# TTGO_shield_revC.net
KiCad netlist of a schematic drawn in EAGLE
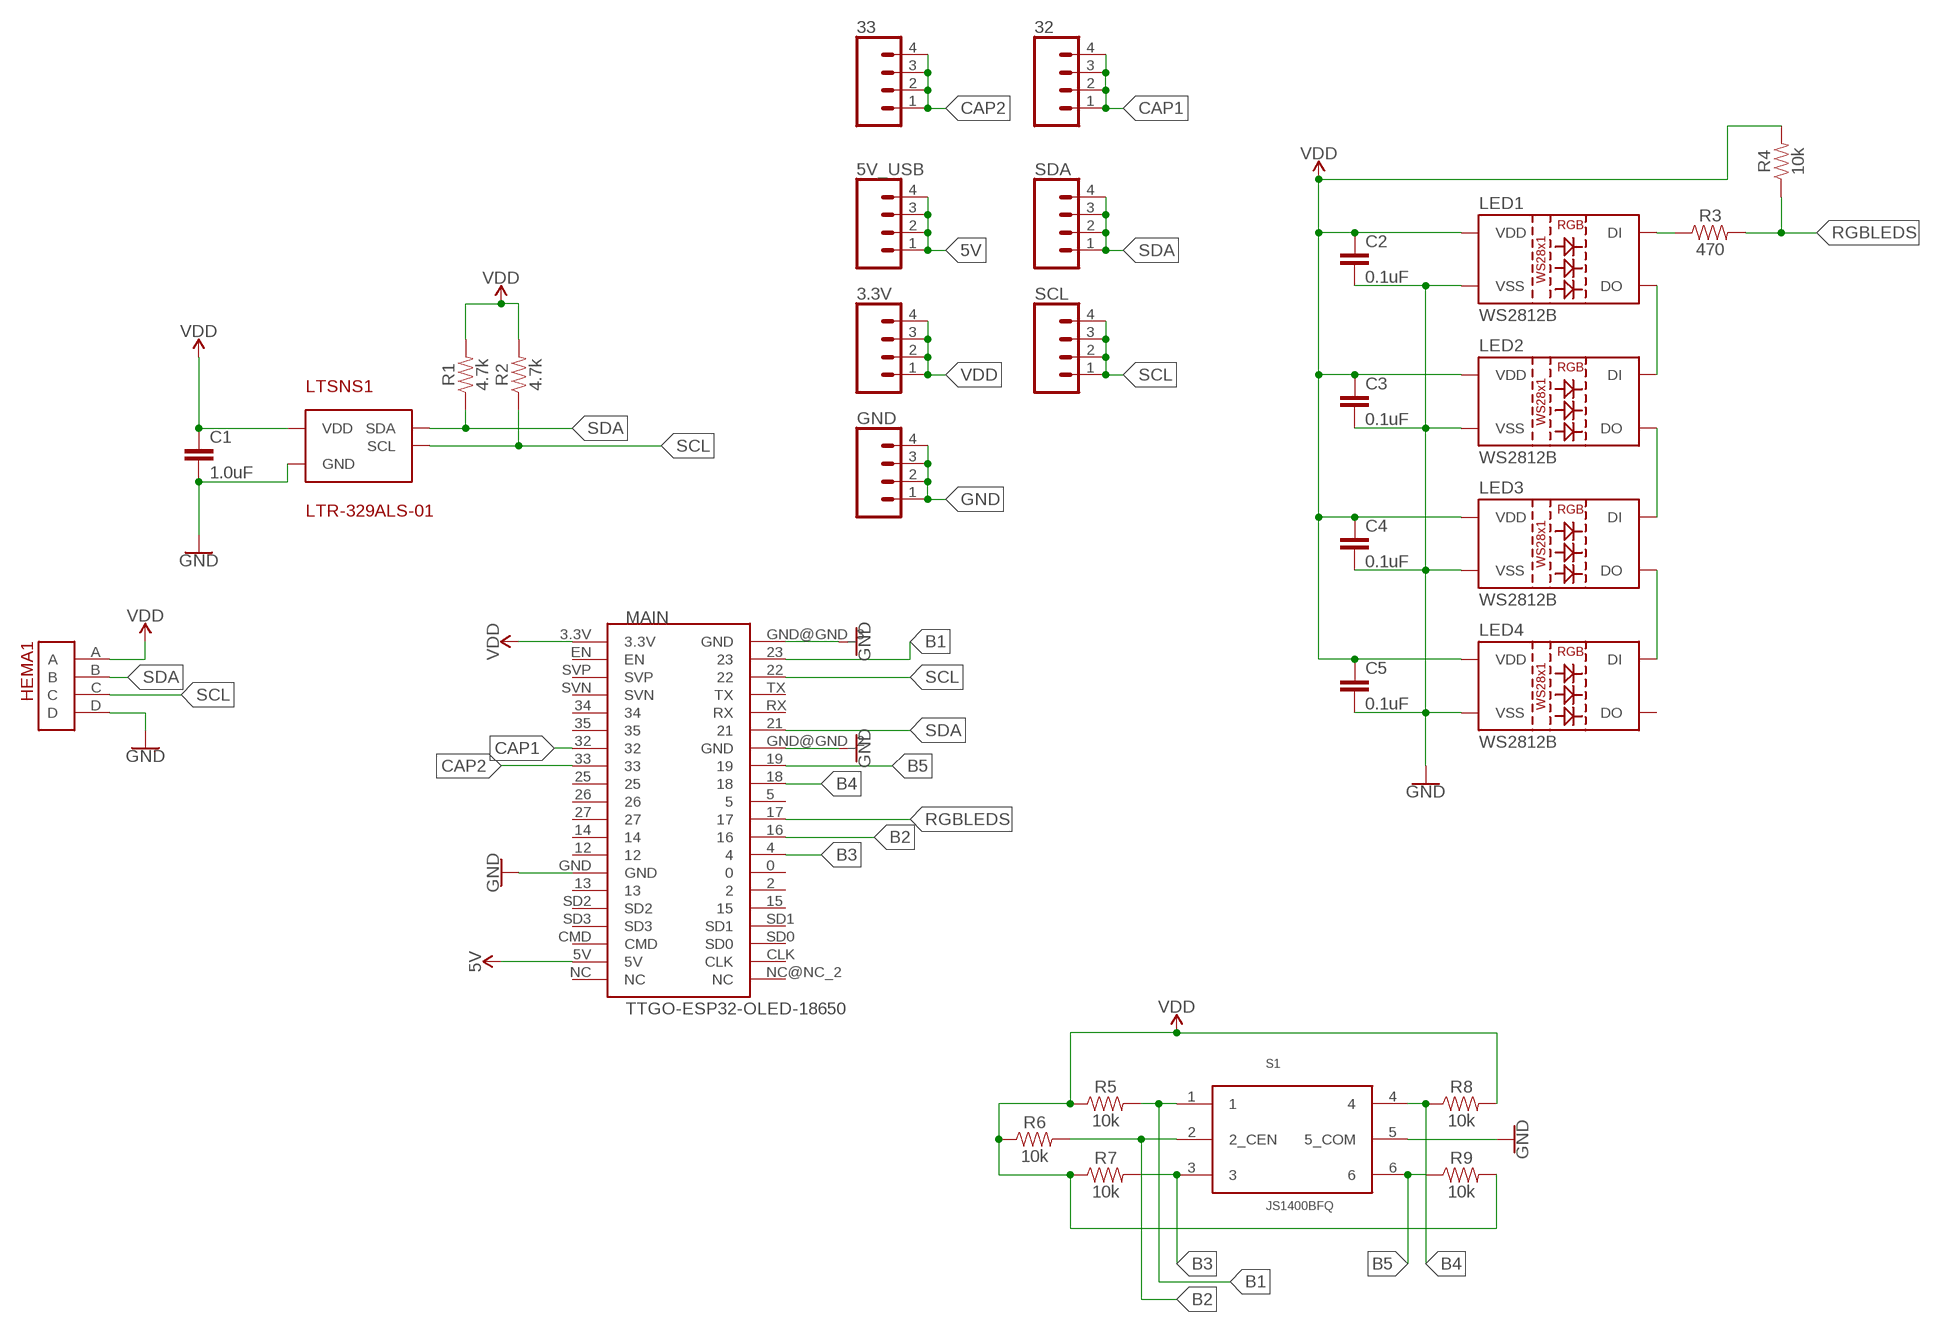
[diagram p0: schematic, sheet 1]

(export (version "E")
  (design (tool "Eeschema 10.0.6"))
  (components
    (comp (ref "3.3V")
      (value "CONN_041X04_NO_SILK")
      (footprint "eagle-import:1X04_NO_SILK")
      (libsource (lib "eagle-import") (part "CONN_041X04_NO_SILK"))
    )
    (comp (ref "5V_USB")
      (value "CONN_041X04_NO_SILK")
      (footprint "eagle-import:1X04_NO_SILK")
      (libsource (lib "eagle-import") (part "CONN_041X04_NO_SILK"))
    )
    (comp (ref "32")
      (value "CONN_041X04_NO_SILK")
      (footprint "eagle-import:1X04_NO_SILK")
      (libsource (lib "eagle-import") (part "CONN_041X04_NO_SILK"))
    )
    (comp (ref "33")
      (value "CONN_041X04_NO_SILK")
      (footprint "eagle-import:1X04_NO_SILK")
      (libsource (lib "eagle-import") (part "CONN_041X04_NO_SILK"))
    )
    (comp (ref "C1")
      (value "1.0uF")
      (footprint "eagle-import:0805")
      (libsource (lib "eagle-import") (part "1.0UF-0805-25V-10%"))
    )
    (comp (ref "C2")
      (value "0.1uF")
      (footprint "eagle-import:0603")
      (libsource (lib "eagle-import") (part "0.1UF-0603-25V-5%"))
    )
    (comp (ref "C3")
      (value "0.1uF")
      (footprint "eagle-import:0603")
      (libsource (lib "eagle-import") (part "0.1UF-0603-25V-5%"))
    )
    (comp (ref "C4")
      (value "0.1uF")
      (footprint "eagle-import:0603")
      (libsource (lib "eagle-import") (part "0.1UF-0603-25V-5%"))
    )
    (comp (ref "C5")
      (value "0.1uF")
      (footprint "eagle-import:0603")
      (libsource (lib "eagle-import") (part "0.1UF-0603-25V-5%"))
    )
    (comp (ref "GND")
      (value "CONN_041X04_NO_SILK")
      (footprint "eagle-import:1X04_NO_SILK")
      (libsource (lib "eagle-import") (part "CONN_041X04_NO_SILK"))
    )
    (comp (ref "HEMA1")
      (value "10120045-400LF")
      (footprint "eagle-import:10120045-400LF")
      (libsource (lib "eagle-import") (part "10120045-400LF"))
    )
    (comp (ref "LED1")
      (value "WS2812B")
      (footprint "eagle-import:WS2812B")
      (libsource (lib "eagle-import") (part "WS2812B"))
    )
    (comp (ref "LED2")
      (value "WS2812B")
      (footprint "eagle-import:WS2812B")
      (libsource (lib "eagle-import") (part "WS2812B"))
    )
    (comp (ref "LED3")
      (value "WS2812B")
      (footprint "eagle-import:WS2812B")
      (libsource (lib "eagle-import") (part "WS2812B"))
    )
    (comp (ref "LED4")
      (value "WS2812B")
      (footprint "eagle-import:WS2812B")
      (libsource (lib "eagle-import") (part "WS2812B"))
    )
    (comp (ref "LTSNS1")
      (value "LTR-329ALS-01")
      (footprint "eagle-import:CHIPLED-4")
      (libsource (lib "eagle-import") (part "LTR-329ALS-01"))
    )
    (comp (ref "MAIN")
      (value "TTGO-ESP32-OLED-18650")
      (footprint "eagle-import:TTGO-ESP32-OLED-18650")
      (libsource (lib "eagle-import") (part "TTGO-ESP32-OLED-18650"))
    )
    (comp (ref "R1")
      (value "4.7k")
      (footprint "eagle-import:0603")
      (libsource (lib "eagle-import") (part "4.7KOHM-0603-1/10W-1%"))
    )
    (comp (ref "R2")
      (value "4.7k")
      (footprint "eagle-import:0603")
      (libsource (lib "eagle-import") (part "4.7KOHM-0603-1/10W-1%"))
    )
    (comp (ref "R3")
      (value "470")
      (footprint "eagle-import:0603")
      (libsource (lib "eagle-import") (part "470OHM-0603-1/10W-1%"))
    )
    (comp (ref "R4")
      (value "10k")
      (footprint "eagle-import:0603")
      (libsource (lib "eagle-import") (part "10KOHM-0603-1/10W-1%"))
    )
    (comp (ref "R5")
      (value "10k")
      (footprint "eagle-import:0603")
      (libsource (lib "eagle-import") (part "10KOHM-0603-1/10W-1%"))
    )
    (comp (ref "R6")
      (value "10k")
      (footprint "eagle-import:0603")
      (libsource (lib "eagle-import") (part "10KOHM-0603-1/10W-1%"))
    )
    (comp (ref "R7")
      (value "10k")
      (footprint "eagle-import:0603")
      (libsource (lib "eagle-import") (part "10KOHM-0603-1/10W-1%"))
    )
    (comp (ref "R8")
      (value "10k")
      (footprint "eagle-import:0603")
      (libsource (lib "eagle-import") (part "10KOHM-0603-1/10W-1%"))
    )
    (comp (ref "R9")
      (value "10k")
      (footprint "eagle-import:0603")
      (libsource (lib "eagle-import") (part "10KOHM-0603-1/10W-1%"))
    )
    (comp (ref "S1")
      (value "JS1400BFQ")
      (footprint "eagle-import:JS1400BFQ")
      (libsource (lib "eagle-import") (part "JS1400BFQ"))
    )
    (comp (ref "SCL")
      (value "CONN_041X04_NO_SILK")
      (footprint "eagle-import:1X04_NO_SILK")
      (libsource (lib "eagle-import") (part "CONN_041X04_NO_SILK"))
    )
    (comp (ref "SDA")
      (value "CONN_041X04_NO_SILK")
      (footprint "eagle-import:1X04_NO_SILK")
      (libsource (lib "eagle-import") (part "CONN_041X04_NO_SILK"))
    )
  )
  (nets
    (net (code "1") (name "5V") (class "Default")
      (node (ref "5V_USB") (pin "1") (pinfunction "1_1") (pintype "passive"))
      (node (ref "5V_USB") (pin "2") (pinfunction "2_2") (pintype "passive"))
      (node (ref "5V_USB") (pin "3") (pinfunction "3_3") (pintype "passive"))
      (node (ref "5V_USB") (pin "4") (pinfunction "4_4") (pintype "passive"))
      (node (ref "MAIN") (pin "5V") (pinfunction "5V_5V") (pintype "bidirectional"))
    )
    (net (code "2") (name "B1") (class "Default")
      (node (ref "MAIN") (pin "23") (pinfunction "23_23") (pintype "bidirectional"))
      (node (ref "R5") (pin "2") (pinfunction "2_2") (pintype "passive"))
      (node (ref "S1") (pin "1") (pinfunction "1_1") (pintype "bidirectional"))
    )
    (net (code "3") (name "B2") (class "Default")
      (node (ref "MAIN") (pin "16") (pinfunction "16_16") (pintype "bidirectional"))
      (node (ref "R6") (pin "2") (pinfunction "2_2") (pintype "passive"))
      (node (ref "S1") (pin "2") (pinfunction "2_CEN_2") (pintype "bidirectional"))
    )
    (net (code "4") (name "B3") (class "Default")
      (node (ref "MAIN") (pin "4") (pinfunction "4_4") (pintype "bidirectional"))
      (node (ref "R7") (pin "2") (pinfunction "2_2") (pintype "passive"))
      (node (ref "S1") (pin "3") (pinfunction "3_3") (pintype "bidirectional"))
    )
    (net (code "5") (name "B4") (class "Default")
      (node (ref "MAIN") (pin "18") (pinfunction "18_18") (pintype "bidirectional"))
      (node (ref "R8") (pin "1") (pinfunction "1_1") (pintype "passive"))
      (node (ref "S1") (pin "4") (pinfunction "4_4") (pintype "bidirectional"))
    )
    (net (code "6") (name "B5") (class "Default")
      (node (ref "MAIN") (pin "19") (pinfunction "19_19") (pintype "bidirectional"))
      (node (ref "R9") (pin "1") (pinfunction "1_1") (pintype "passive"))
      (node (ref "S1") (pin "6") (pinfunction "6_6") (pintype "bidirectional"))
    )
    (net (code "7") (name "CAP1") (class "Default")
      (node (ref "32") (pin "1") (pinfunction "1_1") (pintype "passive"))
      (node (ref "32") (pin "2") (pinfunction "2_2") (pintype "passive"))
      (node (ref "32") (pin "3") (pinfunction "3_3") (pintype "passive"))
      (node (ref "32") (pin "4") (pinfunction "4_4") (pintype "passive"))
      (node (ref "MAIN") (pin "32") (pinfunction "32_32") (pintype "bidirectional"))
    )
    (net (code "8") (name "CAP2") (class "Default")
      (node (ref "33") (pin "1") (pinfunction "1_1") (pintype "passive"))
      (node (ref "33") (pin "2") (pinfunction "2_2") (pintype "passive"))
      (node (ref "33") (pin "3") (pinfunction "3_3") (pintype "passive"))
      (node (ref "33") (pin "4") (pinfunction "4_4") (pintype "passive"))
      (node (ref "MAIN") (pin "33") (pinfunction "33_33") (pintype "bidirectional"))
    )
    (net (code "9") (name "GND") (class "Default")
      (node (ref "C1") (pin "2") (pinfunction "2_2") (pintype "passive"))
      (node (ref "C2") (pin "2") (pinfunction "2_2") (pintype "passive"))
      (node (ref "C3") (pin "2") (pinfunction "2_2") (pintype "passive"))
      (node (ref "C4") (pin "2") (pinfunction "2_2") (pintype "passive"))
      (node (ref "C5") (pin "2") (pinfunction "2_2") (pintype "passive"))
      (node (ref "GND") (pin "1") (pinfunction "1_1") (pintype "passive"))
      (node (ref "GND") (pin "2") (pinfunction "2_2") (pintype "passive"))
      (node (ref "GND") (pin "3") (pinfunction "3_3") (pintype "passive"))
      (node (ref "GND") (pin "4") (pinfunction "4_4") (pintype "passive"))
      (node (ref "HEMA1") (pin "D") (pinfunction "D_D") (pintype "bidirectional"))
      (node (ref "LED1") (pin "3") (pinfunction "VSS_3") (pintype "bidirectional"))
      (node (ref "LED2") (pin "3") (pinfunction "VSS_3") (pintype "bidirectional"))
      (node (ref "LED3") (pin "3") (pinfunction "VSS_3") (pintype "bidirectional"))
      (node (ref "LED4") (pin "3") (pinfunction "VSS_3") (pintype "bidirectional"))
      (node (ref "LTSNS1") (pin "2") (pinfunction "GND_2") (pintype "bidirectional"))
      (node (ref "MAIN") (pin "GND") (pinfunction "GND_GND") (pintype "bidirectional"))
      (node (ref "MAIN") (pin "GND@GND_2") (pinfunction "GND_GND@GND_2") (pintype "bidirectional"))
      (node (ref "MAIN") (pin "GND@GND_3") (pinfunction "GND_GND@GND_3") (pintype "bidirectional"))
      (node (ref "S1") (pin "5") (pinfunction "5_COM_5") (pintype "bidirectional"))
    )
    (net (code "10") (name "Net-(LED1-DI)") (class "Default")
      (node (ref "LED1") (pin "4") (pinfunction "DI_4") (pintype "bidirectional"))
      (node (ref "R3") (pin "1") (pinfunction "1_1") (pintype "passive"))
    )
    (net (code "11") (name "Net-(LED1-DO)") (class "Default")
      (node (ref "LED1") (pin "2") (pinfunction "DO_2") (pintype "bidirectional"))
      (node (ref "LED2") (pin "4") (pinfunction "DI_4") (pintype "bidirectional"))
    )
    (net (code "12") (name "Net-(LED2-DO)") (class "Default")
      (node (ref "LED2") (pin "2") (pinfunction "DO_2") (pintype "bidirectional"))
      (node (ref "LED3") (pin "4") (pinfunction "DI_4") (pintype "bidirectional"))
    )
    (net (code "13") (name "Net-(LED3-DO)") (class "Default")
      (node (ref "LED3") (pin "2") (pinfunction "DO_2") (pintype "bidirectional"))
      (node (ref "LED4") (pin "4") (pinfunction "DI_4") (pintype "bidirectional"))
    )
    (net (code "14") (name "RGBLEDS") (class "Default")
      (node (ref "MAIN") (pin "17") (pinfunction "17_17") (pintype "bidirectional"))
      (node (ref "R3") (pin "2") (pinfunction "2_2") (pintype "passive"))
      (node (ref "R4") (pin "1") (pinfunction "1_1") (pintype "passive"))
    )
    (net (code "15") (name "SCL") (class "Default")
      (node (ref "HEMA1") (pin "C") (pinfunction "C_C") (pintype "bidirectional"))
      (node (ref "LTSNS1") (pin "4") (pinfunction "SCL_4") (pintype "bidirectional"))
      (node (ref "MAIN") (pin "22") (pinfunction "22_22") (pintype "bidirectional"))
      (node (ref "R2") (pin "1") (pinfunction "1_1") (pintype "passive"))
      (node (ref "SCL") (pin "1") (pinfunction "1_1") (pintype "passive"))
      (node (ref "SCL") (pin "2") (pinfunction "2_2") (pintype "passive"))
      (node (ref "SCL") (pin "3") (pinfunction "3_3") (pintype "passive"))
      (node (ref "SCL") (pin "4") (pinfunction "4_4") (pintype "passive"))
    )
    (net (code "16") (name "SDA") (class "Default")
      (node (ref "HEMA1") (pin "B") (pinfunction "B_B") (pintype "bidirectional"))
      (node (ref "LTSNS1") (pin "3") (pinfunction "SDA_3") (pintype "bidirectional"))
      (node (ref "MAIN") (pin "21") (pinfunction "21_21") (pintype "bidirectional"))
      (node (ref "R1") (pin "1") (pinfunction "1_1") (pintype "passive"))
      (node (ref "SDA") (pin "1") (pinfunction "1_1") (pintype "passive"))
      (node (ref "SDA") (pin "2") (pinfunction "2_2") (pintype "passive"))
      (node (ref "SDA") (pin "3") (pinfunction "3_3") (pintype "passive"))
      (node (ref "SDA") (pin "4") (pinfunction "4_4") (pintype "passive"))
    )
    (net (code "17") (name "VDD") (class "Default")
      (node (ref "3.3V") (pin "1") (pinfunction "1_1") (pintype "passive"))
      (node (ref "3.3V") (pin "2") (pinfunction "2_2") (pintype "passive"))
      (node (ref "3.3V") (pin "3") (pinfunction "3_3") (pintype "passive"))
      (node (ref "3.3V") (pin "4") (pinfunction "4_4") (pintype "passive"))
      (node (ref "C1") (pin "1") (pinfunction "1_1") (pintype "passive"))
      (node (ref "C2") (pin "1") (pinfunction "1_1") (pintype "passive"))
      (node (ref "C3") (pin "1") (pinfunction "1_1") (pintype "passive"))
      (node (ref "C4") (pin "1") (pinfunction "1_1") (pintype "passive"))
      (node (ref "C5") (pin "1") (pinfunction "1_1") (pintype "passive"))
      (node (ref "HEMA1") (pin "A") (pinfunction "A_A") (pintype "bidirectional"))
      (node (ref "LED1") (pin "1") (pinfunction "VDD_1") (pintype "bidirectional"))
      (node (ref "LED2") (pin "1") (pinfunction "VDD_1") (pintype "bidirectional"))
      (node (ref "LED3") (pin "1") (pinfunction "VDD_1") (pintype "bidirectional"))
      (node (ref "LED4") (pin "1") (pinfunction "VDD_1") (pintype "bidirectional"))
      (node (ref "LTSNS1") (pin "1") (pinfunction "VDD_1") (pintype "bidirectional"))
      (node (ref "MAIN") (pin "3.3V") (pinfunction "3.3V_3.3V") (pintype "bidirectional"))
      (node (ref "R1") (pin "2") (pinfunction "2_2") (pintype "passive"))
      (node (ref "R2") (pin "2") (pinfunction "2_2") (pintype "passive"))
      (node (ref "R4") (pin "2") (pinfunction "2_2") (pintype "passive"))
      (node (ref "R5") (pin "1") (pinfunction "1_1") (pintype "passive"))
      (node (ref "R6") (pin "1") (pinfunction "1_1") (pintype "passive"))
      (node (ref "R7") (pin "1") (pinfunction "1_1") (pintype "passive"))
      (node (ref "R8") (pin "2") (pinfunction "2_2") (pintype "passive"))
      (node (ref "R9") (pin "2") (pinfunction "2_2") (pintype "passive"))
    )
    (net (code "18") (name "unconnected-(LED4-DO-Pad2)") (class "Default")
      (node (ref "LED4") (pin "2") (pinfunction "DO_2") (pintype "bidirectional"))
    )
    (net (code "19") (name "unconnected-(MAIN-NC-PadNC@NC_2)") (class "Default")
      (node (ref "MAIN") (pin "NC@NC_2") (pinfunction "NC_NC@NC_2") (pintype "bidirectional"))
    )
    (net (code "20") (name "unconnected-(MAIN-Pad0)") (class "Default")
      (node (ref "MAIN") (pin "0") (pinfunction "0_0") (pintype "bidirectional"))
    )
    (net (code "21") (name "unconnected-(MAIN-Pad2)") (class "Default")
      (node (ref "MAIN") (pin "2") (pinfunction "2_2") (pintype "bidirectional"))
    )
    (net (code "22") (name "unconnected-(MAIN-Pad5)") (class "Default")
      (node (ref "MAIN") (pin "5") (pinfunction "5_5") (pintype "bidirectional"))
    )
    (net (code "23") (name "unconnected-(MAIN-Pad12)") (class "Default")
      (node (ref "MAIN") (pin "12") (pinfunction "12_12") (pintype "bidirectional"))
    )
    (net (code "24") (name "unconnected-(MAIN-Pad13)") (class "Default")
      (node (ref "MAIN") (pin "13") (pinfunction "13_13") (pintype "bidirectional"))
    )
    (net (code "25") (name "unconnected-(MAIN-Pad14)") (class "Default")
      (node (ref "MAIN") (pin "14") (pinfunction "14_14") (pintype "bidirectional"))
    )
    (net (code "26") (name "unconnected-(MAIN-Pad15)") (class "Default")
      (node (ref "MAIN") (pin "15") (pinfunction "15_15") (pintype "bidirectional"))
    )
    (net (code "27") (name "unconnected-(MAIN-Pad25)") (class "Default")
      (node (ref "MAIN") (pin "25") (pinfunction "25_25") (pintype "bidirectional"))
    )
    (net (code "28") (name "unconnected-(MAIN-Pad26)") (class "Default")
      (node (ref "MAIN") (pin "26") (pinfunction "26_26") (pintype "bidirectional"))
    )
    (net (code "29") (name "unconnected-(MAIN-Pad27)") (class "Default")
      (node (ref "MAIN") (pin "27") (pinfunction "27_27") (pintype "bidirectional"))
    )
    (net (code "30") (name "unconnected-(MAIN-Pad34)") (class "Default")
      (node (ref "MAIN") (pin "34") (pinfunction "34_34") (pintype "bidirectional"))
    )
    (net (code "31") (name "unconnected-(MAIN-Pad35)") (class "Default")
      (node (ref "MAIN") (pin "35") (pinfunction "35_35") (pintype "bidirectional"))
    )
    (net (code "32") (name "unconnected-(MAIN-PadCLK)") (class "Default")
      (node (ref "MAIN") (pin "CLK") (pinfunction "CLK_CLK") (pintype "bidirectional"))
    )
    (net (code "33") (name "unconnected-(MAIN-PadCMD)") (class "Default")
      (node (ref "MAIN") (pin "CMD") (pinfunction "CMD_CMD") (pintype "bidirectional"))
    )
    (net (code "34") (name "unconnected-(MAIN-PadEN)") (class "Default")
      (node (ref "MAIN") (pin "EN") (pinfunction "EN_EN") (pintype "bidirectional"))
    )
    (net (code "35") (name "unconnected-(MAIN-PadNC)") (class "Default")
      (node (ref "MAIN") (pin "NC") (pinfunction "NC_NC") (pintype "bidirectional"))
    )
    (net (code "36") (name "unconnected-(MAIN-PadRX)") (class "Default")
      (node (ref "MAIN") (pin "RX") (pinfunction "RX_RX") (pintype "bidirectional"))
    )
    (net (code "37") (name "unconnected-(MAIN-PadSD0)") (class "Default")
      (node (ref "MAIN") (pin "SD0") (pinfunction "SD0_SD0") (pintype "bidirectional"))
    )
    (net (code "38") (name "unconnected-(MAIN-PadSD1)") (class "Default")
      (node (ref "MAIN") (pin "SD1") (pinfunction "SD1_SD1") (pintype "bidirectional"))
    )
    (net (code "39") (name "unconnected-(MAIN-PadSD2)") (class "Default")
      (node (ref "MAIN") (pin "SD2") (pinfunction "SD2_SD2") (pintype "bidirectional"))
    )
    (net (code "40") (name "unconnected-(MAIN-PadSD3)") (class "Default")
      (node (ref "MAIN") (pin "SD3") (pinfunction "SD3_SD3") (pintype "bidirectional"))
    )
    (net (code "41") (name "unconnected-(MAIN-PadSVN)") (class "Default")
      (node (ref "MAIN") (pin "SVN") (pinfunction "SVN_SVN") (pintype "bidirectional"))
    )
    (net (code "42") (name "unconnected-(MAIN-PadSVP)") (class "Default")
      (node (ref "MAIN") (pin "SVP") (pinfunction "SVP_SVP") (pintype "bidirectional"))
    )
    (net (code "43") (name "unconnected-(MAIN-PadTX)") (class "Default")
      (node (ref "MAIN") (pin "TX") (pinfunction "TX_TX") (pintype "bidirectional"))
    )
  )
)
